# mainboard.net
KiCad netlist of a schematic drawn in EAGLE
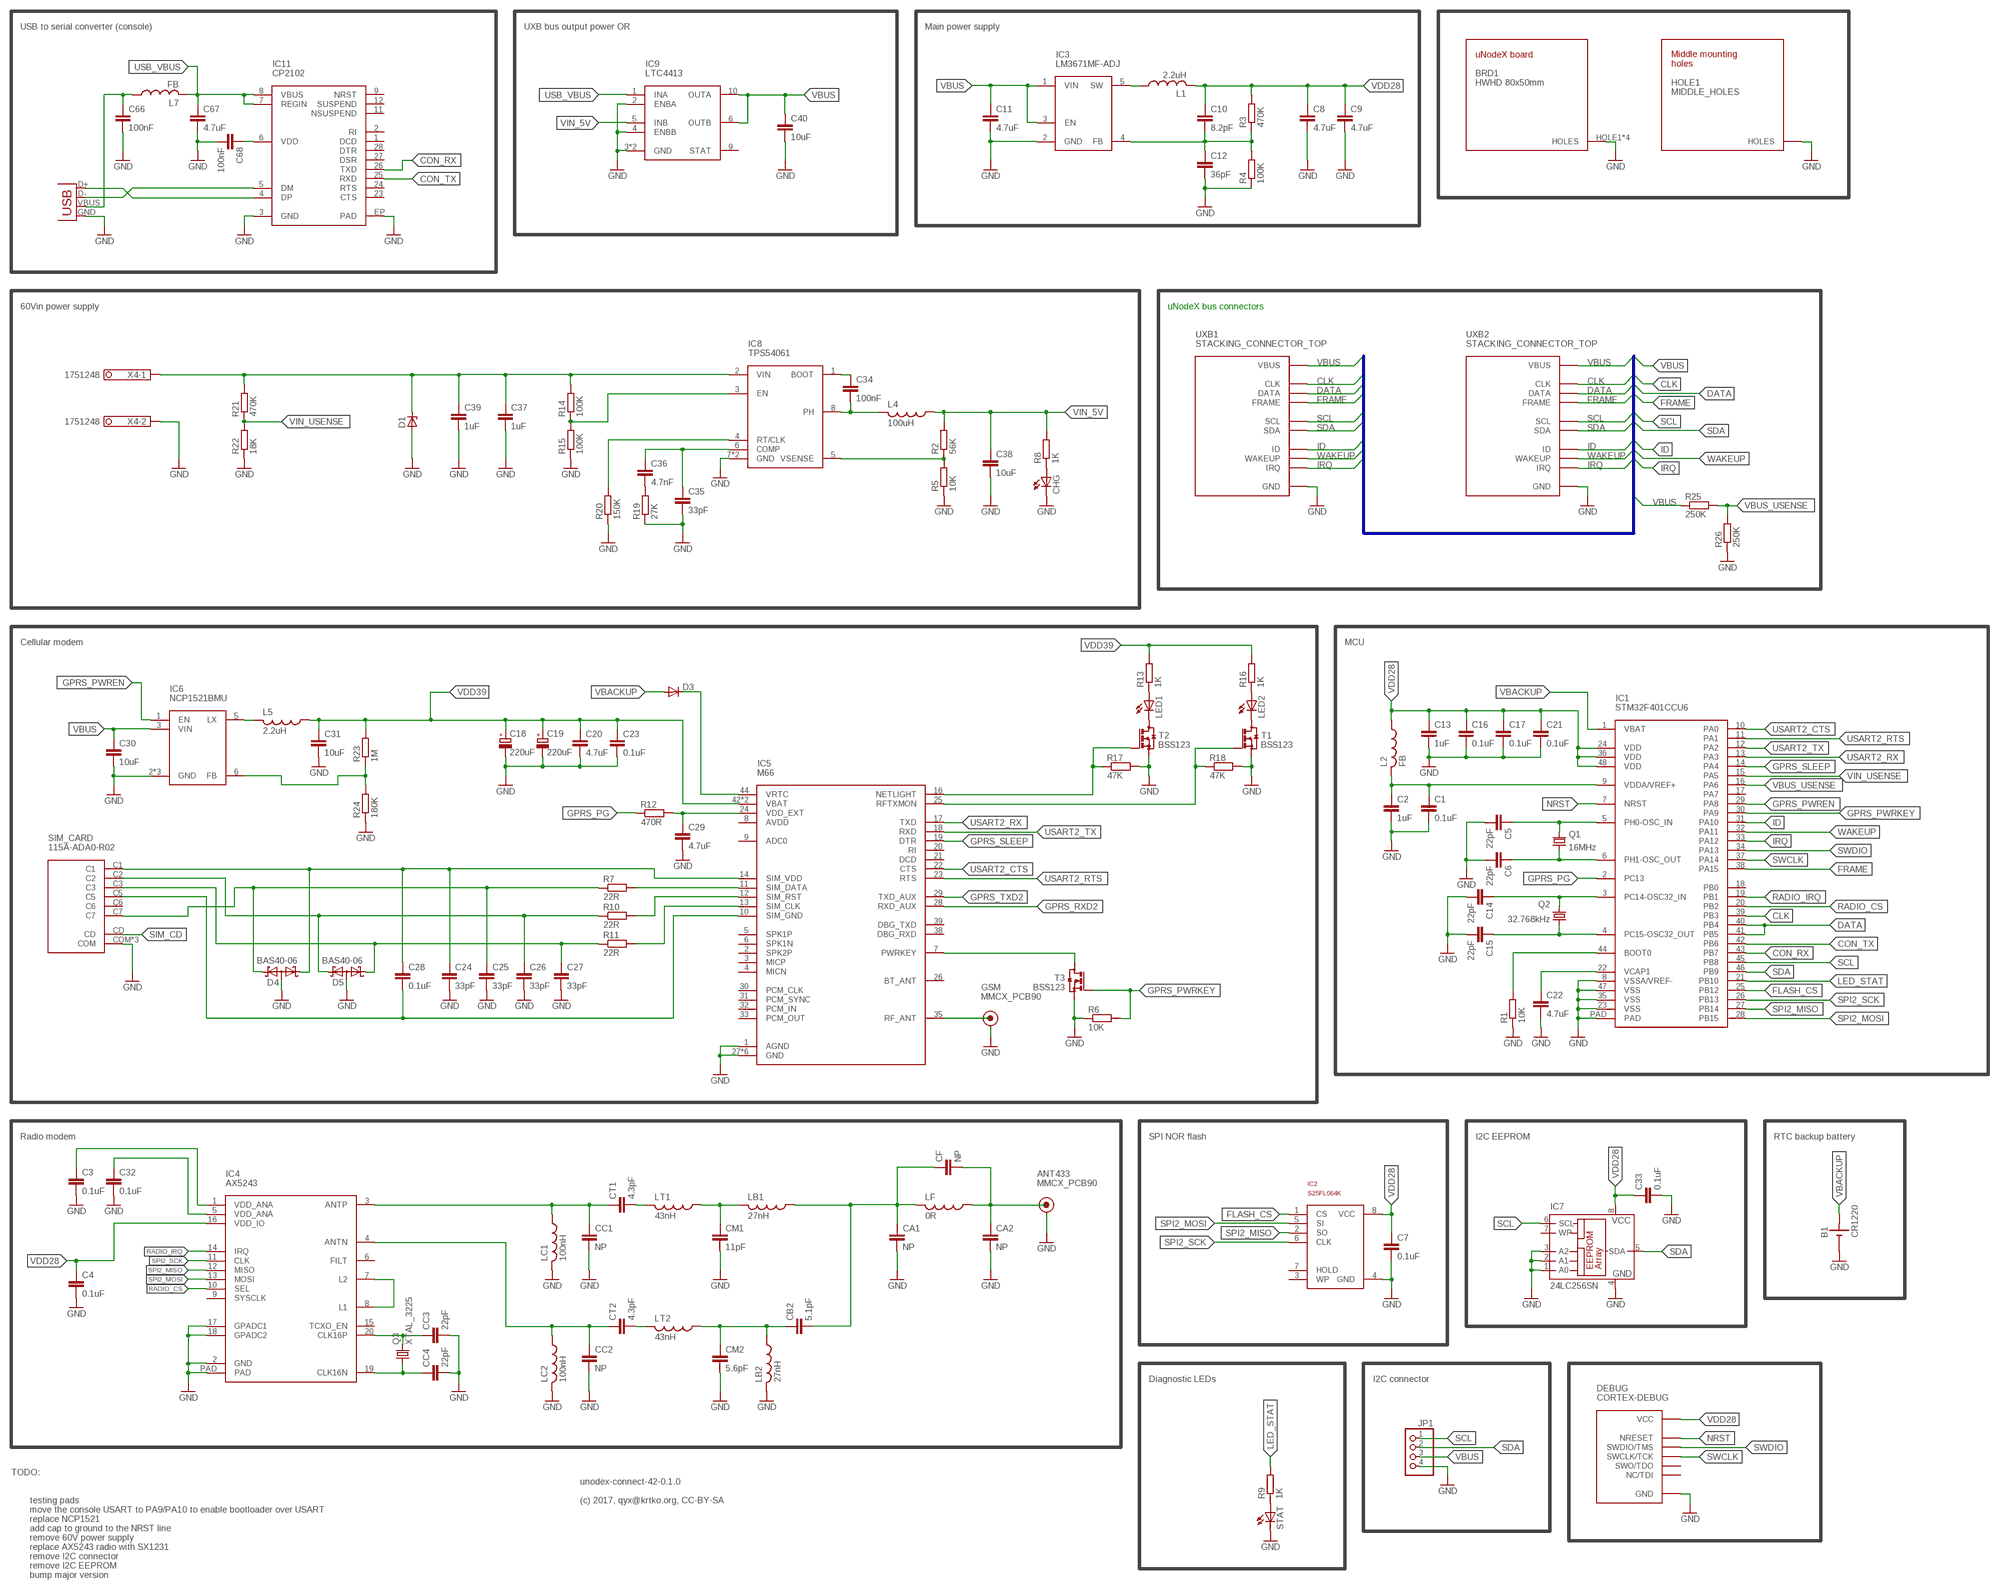
[diagram p0: schematic, sheet 1]

(export (version "E")
  (design (tool "Eeschema 10.0.6"))
  (components
    (comp (ref "ANT433")
      (value "MMCX_PCB90")
      (footprint "eagle-import:MMCX_PCB_90")
      (libsource (lib "eagle-import") (part "MMCX_PCB90"))
    )
    (comp (ref "B1")
      (value "CR1220")
      (footprint "eagle-import:CONNFLY_CR1220")
      (libsource (lib "eagle-import") (part "CONNFLY_CR1220"))
    )
    (comp (ref "BRD1")
      (value "HWHD 80x50mm")
      (footprint "eagle-import:HWHD_SHARP_CORNERS")
      (libsource (lib "eagle-import") (part "BOARD_STACKINGHWHD_SH"))
    )
    (comp (ref "C1")
      (value "0.1uF")
      (footprint "eagle-import:C0603")
      (libsource (lib "eagle-import") (part "C-EUC0603"))
    )
    (comp (ref "C2")
      (value "1uF")
      (footprint "eagle-import:C0603")
      (libsource (lib "eagle-import") (part "C-EUC0603"))
    )
    (comp (ref "C3")
      (value "0.1uF")
      (footprint "eagle-import:C0603")
      (libsource (lib "eagle-import") (part "C-EUC0603"))
    )
    (comp (ref "C4")
      (value "0.1uF")
      (footprint "eagle-import:C0603")
      (libsource (lib "eagle-import") (part "C-EUC0603"))
    )
    (comp (ref "C5")
      (value "22pF")
      (footprint "eagle-import:C0603")
      (libsource (lib "eagle-import") (part "C-EUC0603"))
    )
    (comp (ref "C6")
      (value "22pF")
      (footprint "eagle-import:C0603")
      (libsource (lib "eagle-import") (part "C-EUC0603"))
    )
    (comp (ref "C7")
      (value "0.1uF")
      (footprint "eagle-import:C0603")
      (libsource (lib "eagle-import") (part "C-EUC0603"))
    )
    (comp (ref "C8")
      (value "4.7uF")
      (footprint "eagle-import:C0805")
      (libsource (lib "eagle-import") (part "C-EUC0805"))
    )
    (comp (ref "C9")
      (value "4.7uF")
      (footprint "eagle-import:C0805")
      (libsource (lib "eagle-import") (part "C-EUC0805"))
    )
    (comp (ref "C10")
      (value "8.2pF")
      (footprint "eagle-import:C0603")
      (libsource (lib "eagle-import") (part "C-EUC0603"))
    )
    (comp (ref "C11")
      (value "4.7uF")
      (footprint "eagle-import:C0805")
      (libsource (lib "eagle-import") (part "C-EUC0805"))
    )
    (comp (ref "C12")
      (value "36pF")
      (footprint "eagle-import:C0603")
      (libsource (lib "eagle-import") (part "C-EUC0603"))
    )
    (comp (ref "C13")
      (value "1uF")
      (footprint "eagle-import:C0603")
      (libsource (lib "eagle-import") (part "C-EUC0603"))
    )
    (comp (ref "C14")
      (value "22pF")
      (footprint "eagle-import:C0603")
      (libsource (lib "eagle-import") (part "C-EUC0603"))
    )
    (comp (ref "C15")
      (value "22pF")
      (footprint "eagle-import:C0603")
      (libsource (lib "eagle-import") (part "C-EUC0603"))
    )
    (comp (ref "C16")
      (value "0.1uF")
      (footprint "eagle-import:C0603")
      (libsource (lib "eagle-import") (part "C-EUC0603"))
    )
    (comp (ref "C17")
      (value "0.1uF")
      (footprint "eagle-import:C0603")
      (libsource (lib "eagle-import") (part "C-EUC0603"))
    )
    (comp (ref "C18")
      (value "220uF")
      (footprint "eagle-import:PANASONIC_D")
      (libsource (lib "eagle-import") (part "CPOL-EUD"))
    )
    (comp (ref "C19")
      (value "220uF")
      (footprint "eagle-import:PANASONIC_D")
      (libsource (lib "eagle-import") (part "CPOL-EUD"))
    )
    (comp (ref "C20")
      (value "4.7uF")
      (footprint "eagle-import:C0805")
      (libsource (lib "eagle-import") (part "C-EUC0805"))
    )
    (comp (ref "C21")
      (value "0.1uF")
      (footprint "eagle-import:C0603")
      (libsource (lib "eagle-import") (part "C-EUC0603"))
    )
    (comp (ref "C22")
      (value "4.7uF")
      (footprint "eagle-import:C0603")
      (libsource (lib "eagle-import") (part "C-EUC0603"))
    )
    (comp (ref "C23")
      (value "0.1uF")
      (footprint "eagle-import:C0603")
      (libsource (lib "eagle-import") (part "C-EUC0603"))
    )
    (comp (ref "C24")
      (value "33pF")
      (footprint "eagle-import:C0603")
      (libsource (lib "eagle-import") (part "C-EUC0603"))
    )
    (comp (ref "C25")
      (value "33pF")
      (footprint "eagle-import:C0603")
      (libsource (lib "eagle-import") (part "C-EUC0603"))
    )
    (comp (ref "C26")
      (value "33pF")
      (footprint "eagle-import:C0603")
      (libsource (lib "eagle-import") (part "C-EUC0603"))
    )
    (comp (ref "C27")
      (value "33pF")
      (footprint "eagle-import:C0603")
      (libsource (lib "eagle-import") (part "C-EUC0603"))
    )
    (comp (ref "C28")
      (value "0.1uF")
      (footprint "eagle-import:C0603")
      (libsource (lib "eagle-import") (part "C-EUC0603"))
    )
    (comp (ref "C29")
      (value "4.7uF")
      (footprint "eagle-import:C0805")
      (libsource (lib "eagle-import") (part "C-EUC0805"))
    )
    (comp (ref "C30")
      (value "10uF")
      (footprint "eagle-import:C1206")
      (libsource (lib "eagle-import") (part "C-EUC1206"))
    )
    (comp (ref "C31")
      (value "10uF")
      (footprint "eagle-import:C1206")
      (libsource (lib "eagle-import") (part "C-EUC1206"))
    )
    (comp (ref "C32")
      (value "0.1uF")
      (footprint "eagle-import:C0603")
      (libsource (lib "eagle-import") (part "C-EUC0603"))
    )
    (comp (ref "C33")
      (value "0.1uF")
      (footprint "eagle-import:C0603")
      (libsource (lib "eagle-import") (part "C-EUC0603"))
    )
    (comp (ref "C34")
      (value "100nF")
      (footprint "eagle-import:C0603")
      (libsource (lib "eagle-import") (part "C-EUC0603"))
    )
    (comp (ref "C35")
      (value "33pF")
      (footprint "eagle-import:C0603")
      (libsource (lib "eagle-import") (part "C-EUC0603"))
    )
    (comp (ref "C36")
      (value "4.7nF")
      (footprint "eagle-import:C0603")
      (libsource (lib "eagle-import") (part "C-EUC0603"))
    )
    (comp (ref "C37")
      (value "1uF")
      (footprint "eagle-import:C1206")
      (libsource (lib "eagle-import") (part "C-EUC1206"))
    )
    (comp (ref "C38")
      (value "10uF")
      (footprint "eagle-import:C1206")
      (libsource (lib "eagle-import") (part "C-EUC1206"))
    )
    (comp (ref "C39")
      (value "1uF")
      (footprint "eagle-import:C1206")
      (libsource (lib "eagle-import") (part "C-EUC1206"))
    )
    (comp (ref "C40")
      (value "10uF")
      (footprint "eagle-import:C0805")
      (libsource (lib "eagle-import") (part "C-EUC0805"))
    )
    (comp (ref "C66")
      (value "100nF")
      (footprint "eagle-import:C0603")
      (libsource (lib "eagle-import") (part "C-EUC0603"))
    )
    (comp (ref "C67")
      (value "4.7uF")
      (footprint "eagle-import:C0805")
      (libsource (lib "eagle-import") (part "C-EUC0805"))
    )
    (comp (ref "C68")
      (value "100nF")
      (footprint "eagle-import:C0603")
      (libsource (lib "eagle-import") (part "C-EUC0603"))
    )
    (comp (ref "CA1")
      (value "NP")
      (footprint "eagle-import:C0603")
      (libsource (lib "eagle-import") (part "C-EUC0603"))
    )
    (comp (ref "CA2")
      (value "NP")
      (footprint "eagle-import:C0603")
      (libsource (lib "eagle-import") (part "C-EUC0603"))
    )
    (comp (ref "CB2")
      (value "5.1pF")
      (footprint "eagle-import:C0603")
      (libsource (lib "eagle-import") (part "C-EUC0603"))
    )
    (comp (ref "CC1")
      (value "NP")
      (footprint "eagle-import:C0603")
      (libsource (lib "eagle-import") (part "C-EUC0603"))
    )
    (comp (ref "CC2")
      (value "NP")
      (footprint "eagle-import:C0603")
      (libsource (lib "eagle-import") (part "C-EUC0603"))
    )
    (comp (ref "CC3")
      (value "22pF")
      (footprint "eagle-import:C0603")
      (libsource (lib "eagle-import") (part "C-EUC0603"))
    )
    (comp (ref "CC4")
      (value "22pF")
      (footprint "eagle-import:C0603")
      (libsource (lib "eagle-import") (part "C-EUC0603"))
    )
    (comp (ref "CF")
      (value "NP")
      (footprint "eagle-import:C0603")
      (libsource (lib "eagle-import") (part "C-EUC0603"))
    )
    (comp (ref "CHG")
      (value "LEDCHIPLED_0805")
      (footprint "eagle-import:CHIPLED_0805")
      (libsource (lib "eagle-import") (part "LEDCHIPLED_0805"))
    )
    (comp (ref "CM1")
      (value "11pF")
      (footprint "eagle-import:C0603")
      (libsource (lib "eagle-import") (part "C-EUC0603"))
    )
    (comp (ref "CM2")
      (value "5.6pF")
      (footprint "eagle-import:C0603")
      (libsource (lib "eagle-import") (part "C-EUC0603"))
    )
    (comp (ref "CT1")
      (value "4.3pF")
      (footprint "eagle-import:C0603")
      (libsource (lib "eagle-import") (part "C-EUC0603"))
    )
    (comp (ref "CT2")
      (value "4.3pF")
      (footprint "eagle-import:C0603")
      (libsource (lib "eagle-import") (part "C-EUC0603"))
    )
    (comp (ref "D1")
      (value "ZENER-DIODESMB")
      (footprint "eagle-import:SMB")
      (libsource (lib "eagle-import") (part "ZENER-DIODESMB"))
    )
    (comp (ref "D3")
      (value "DIODE-SOD123")
      (footprint "eagle-import:SOD123")
      (libsource (lib "eagle-import") (part "DIODE-SOD123"))
    )
    (comp (ref "D4")
      (value "BAS40-06")
      (footprint "eagle-import:SOT23")
      (libsource (lib "eagle-import") (part "BAS40-06"))
    )
    (comp (ref "D5")
      (value "BAS40-06")
      (footprint "eagle-import:SOT23")
      (libsource (lib "eagle-import") (part "BAS40-06"))
    )
    (comp (ref "DEBUG")
      (value "CORTEX-DEBUG")
      (footprint "eagle-import:CORTEX-DEBUG")
      (libsource (lib "eagle-import") (part "CORTEX-DEBUG"))
    )
    (comp (ref "GSM")
      (value "MMCX_PCB90")
      (footprint "eagle-import:MMCX_PCB_90")
      (libsource (lib "eagle-import") (part "MMCX_PCB90"))
    )
    (comp (ref "HOLE1")
      (value "MIDDLE_HOLES")
      (footprint "eagle-import:MIDDLE_HOLES")
      (libsource (lib "eagle-import") (part "MIDDLE_HOLES"))
    )
    (comp (ref "IC1")
      (value "STM32F401CCU6")
      (footprint "eagle-import:UFQFPN48")
      (libsource (lib "eagle-import") (part "STM32F401CCU6"))
    )
    (comp (ref "IC2")
      (value "S25FL064K")
      (footprint "eagle-import:SO-08M")
      (libsource (lib "eagle-import") (part "S25FL064K"))
    )
    (comp (ref "IC3")
      (value "LM3671MF-ADJ")
      (footprint "eagle-import:SOT23-5")
      (libsource (lib "eagle-import") (part "LM3671MF"))
    )
    (comp (ref "IC4")
      (value "AX5243")
      (footprint "eagle-import:QFN20")
      (libsource (lib "eagle-import") (part "AX5243"))
    )
    (comp (ref "IC5")
      (value "M66")
      (footprint "eagle-import:M66")
      (libsource (lib "eagle-import") (part "M66"))
    )
    (comp (ref "IC6")
      (value "NCP1521BMU")
      (footprint "eagle-import:UDFN6")
      (libsource (lib "eagle-import") (part "NCP1521BMU"))
    )
    (comp (ref "IC7")
      (value "24LC256SN")
      (footprint "eagle-import:SO-08")
      (fields (field (name "MF") "MICROCHIP") (field (name "MPN") "24LC256-I/SN"))
      (libsource (lib "eagle-import") (part "24SNLC256"))
    )
    (comp (ref "IC8")
      (value "TPS54061")
      (footprint "eagle-import:WSON8")
      (libsource (lib "eagle-import") (part "TPS54061"))
    )
    (comp (ref "IC9")
      (value "LTC4413")
      (footprint "eagle-import:DFN10")
      (libsource (lib "eagle-import") (part "LTC4413"))
    )
    (comp (ref "IC11")
      (value "CP2102")
      (footprint "eagle-import:QFN28")
      (libsource (lib "eagle-import") (part "CP2102"))
    )
    (comp (ref "JP1")
      (value "PINHD-1X4")
      (footprint "eagle-import:1X04")
      (libsource (lib "eagle-import") (part "PINHD-1X4"))
    )
    (comp (ref "L1")
      (value "2.2uH")
      (footprint "eagle-import:L2825P")
      (libsource (lib "eagle-import") (part "L-USL2825P"))
    )
    (comp (ref "L2")
      (value "FB")
      (footprint "eagle-import:L2012C")
      (libsource (lib "eagle-import") (part "L-USL2012C"))
    )
    (comp (ref "L4")
      (value "100uH")
      (footprint "eagle-import:L5650M")
      (libsource (lib "eagle-import") (part "L-USL5650M"))
    )
    (comp (ref "L5")
      (value "2.2uH")
      (footprint "eagle-import:L2825P")
      (libsource (lib "eagle-import") (part "L-USL2825P"))
    )
    (comp (ref "L7")
      (value "FB")
      (footprint "eagle-import:L2012C")
      (libsource (lib "eagle-import") (part "L-USL2012C"))
    )
    (comp (ref "LB1")
      (value "27nH")
      (footprint "eagle-import:L2012C")
      (libsource (lib "eagle-import") (part "L-USL2012C"))
    )
    (comp (ref "LB2")
      (value "27nH")
      (footprint "eagle-import:L2012C")
      (libsource (lib "eagle-import") (part "L-USL2012C"))
    )
    (comp (ref "LC1")
      (value "100nH")
      (footprint "eagle-import:L2012C")
      (libsource (lib "eagle-import") (part "L-USL2012C"))
    )
    (comp (ref "LC2")
      (value "100nH")
      (footprint "eagle-import:L2012C")
      (libsource (lib "eagle-import") (part "L-USL2012C"))
    )
    (comp (ref "LED1")
      (value "LEDCHIP-LED0805")
      (footprint "eagle-import:CHIP-LED0805")
      (libsource (lib "eagle-import") (part "LEDCHIP-LED0805"))
    )
    (comp (ref "LED2")
      (value "LEDCHIP-LED0805")
      (footprint "eagle-import:CHIP-LED0805")
      (libsource (lib "eagle-import") (part "LEDCHIP-LED0805"))
    )
    (comp (ref "LF")
      (value "0R")
      (footprint "eagle-import:L2012C")
      (libsource (lib "eagle-import") (part "L-USL2012C"))
    )
    (comp (ref "LT1")
      (value "43nH")
      (footprint "eagle-import:L2012C")
      (libsource (lib "eagle-import") (part "L-USL2012C"))
    )
    (comp (ref "LT2")
      (value "43nH")
      (footprint "eagle-import:L2012C")
      (libsource (lib "eagle-import") (part "L-USL2012C"))
    )
    (comp (ref "Q1")
      (value "16MHz")
      (footprint "eagle-import:XTAL_3225")
      (libsource (lib "eagle-import") (part "XTAL_3225"))
    )
    (comp (ref "Q2")
      (value "32.768kHz")
      (footprint "eagle-import:TC26H")
      (libsource (lib "eagle-import") (part "CRYSTALTC26H"))
    )
    (comp (ref "Q3")
      (value "XTAL_3225")
      (footprint "eagle-import:XTAL_3225")
      (libsource (lib "eagle-import") (part "XTAL_3225"))
    )
    (comp (ref "R1")
      (value "10K")
      (footprint "eagle-import:R0603")
      (libsource (lib "eagle-import") (part "R-EU_R0603"))
    )
    (comp (ref "R2")
      (value "56K")
      (footprint "eagle-import:R0603")
      (libsource (lib "eagle-import") (part "R-EU_R0603"))
    )
    (comp (ref "R3")
      (value "470K")
      (footprint "eagle-import:R0603")
      (libsource (lib "eagle-import") (part "R-EU_R0603"))
    )
    (comp (ref "R4")
      (value "100K")
      (footprint "eagle-import:R0603")
      (libsource (lib "eagle-import") (part "R-EU_R0603"))
    )
    (comp (ref "R5")
      (value "10K")
      (footprint "eagle-import:R0603")
      (libsource (lib "eagle-import") (part "R-EU_R0603"))
    )
    (comp (ref "R6")
      (value "10K")
      (footprint "eagle-import:R0603")
      (libsource (lib "eagle-import") (part "R-EU_R0603"))
    )
    (comp (ref "R7")
      (value "22R")
      (footprint "eagle-import:R0603")
      (libsource (lib "eagle-import") (part "R-EU_R0603"))
    )
    (comp (ref "R8")
      (value "1K")
      (footprint "eagle-import:R0603")
      (libsource (lib "eagle-import") (part "R-EU_R0603"))
    )
    (comp (ref "R9")
      (value "1K")
      (footprint "eagle-import:R0603")
      (libsource (lib "eagle-import") (part "R-EU_R0603"))
    )
    (comp (ref "R10")
      (value "22R")
      (footprint "eagle-import:R0603")
      (libsource (lib "eagle-import") (part "R-EU_R0603"))
    )
    (comp (ref "R11")
      (value "22R")
      (footprint "eagle-import:R0603")
      (libsource (lib "eagle-import") (part "R-EU_R0603"))
    )
    (comp (ref "R12")
      (value "470R")
      (footprint "eagle-import:R0603")
      (libsource (lib "eagle-import") (part "R-EU_R0603"))
    )
    (comp (ref "R13")
      (value "1K")
      (footprint "eagle-import:R0603")
      (libsource (lib "eagle-import") (part "R-EU_R0603"))
    )
    (comp (ref "R14")
      (value "100K")
      (footprint "eagle-import:R0603")
      (libsource (lib "eagle-import") (part "R-EU_R0603"))
    )
    (comp (ref "R15")
      (value "100K")
      (footprint "eagle-import:R0603")
      (libsource (lib "eagle-import") (part "R-EU_R0603"))
    )
    (comp (ref "R16")
      (value "1K")
      (footprint "eagle-import:R0603")
      (libsource (lib "eagle-import") (part "R-EU_R0603"))
    )
    (comp (ref "R17")
      (value "47K")
      (footprint "eagle-import:R0603")
      (libsource (lib "eagle-import") (part "R-EU_R0603"))
    )
    (comp (ref "R18")
      (value "47K")
      (footprint "eagle-import:R0603")
      (libsource (lib "eagle-import") (part "R-EU_R0603"))
    )
    (comp (ref "R19")
      (value "27K")
      (footprint "eagle-import:R0603")
      (libsource (lib "eagle-import") (part "R-EU_R0603"))
    )
    (comp (ref "R20")
      (value "150K")
      (footprint "eagle-import:R0603")
      (libsource (lib "eagle-import") (part "R-EU_R0603"))
    )
    (comp (ref "R21")
      (value "470K")
      (footprint "eagle-import:R0603")
      (libsource (lib "eagle-import") (part "R-EU_R0603"))
    )
    (comp (ref "R22")
      (value "18K")
      (footprint "eagle-import:R0603")
      (libsource (lib "eagle-import") (part "R-EU_R0603"))
    )
    (comp (ref "R23")
      (value "1M")
      (footprint "eagle-import:R0603")
      (libsource (lib "eagle-import") (part "R-EU_R0603"))
    )
    (comp (ref "R24")
      (value "180K")
      (footprint "eagle-import:R0603")
      (libsource (lib "eagle-import") (part "R-EU_R0603"))
    )
    (comp (ref "R25")
      (value "250K")
      (footprint "eagle-import:R0603")
      (libsource (lib "eagle-import") (part "R-EU_R0603"))
    )
    (comp (ref "R26")
      (value "250K")
      (footprint "eagle-import:R0603")
      (libsource (lib "eagle-import") (part "R-EU_R0603"))
    )
    (comp (ref "SIM_CARD")
      (value "115A-ADA0-R02")
      (footprint "eagle-import:115A-ADA0-R02")
      (libsource (lib "eagle-import") (part "115A-ADA0-R02"))
    )
    (comp (ref "STAT")
      (value "LEDCHIPLED_0805")
      (footprint "eagle-import:CHIPLED_0805")
      (libsource (lib "eagle-import") (part "LEDCHIPLED_0805"))
    )
    (comp (ref "T1")
      (value "BSS123")
      (footprint "eagle-import:SOT23")
      (libsource (lib "eagle-import") (part "BSS123"))
    )
    (comp (ref "T2")
      (value "BSS123")
      (footprint "eagle-import:SOT23")
      (libsource (lib "eagle-import") (part "BSS123"))
    )
    (comp (ref "T3")
      (value "BSS123")
      (footprint "eagle-import:SOT23")
      (libsource (lib "eagle-import") (part "BSS123"))
    )
    (comp (ref "UXB1")
      (value "STACKING_CONNECTOR_TOP")
      (footprint "eagle-import:HAR-FLEX-TOP-12P")
      (libsource (lib "eagle-import") (part "STACKING_CONNECTOR_TOP"))
    )
    (comp (ref "UXB2")
      (value "STACKING_CONNECTOR_TOP")
      (footprint "eagle-import:HAR-FLEX-TOP-12P")
      (libsource (lib "eagle-import") (part "STACKING_CONNECTOR_TOP"))
    )
    (comp (ref "X4")
      (value "1751248")
      (footprint "eagle-import:1751248")
      (libsource (lib "eagle-import") (part "1751248"))
    )
    (comp (ref "X5")
      (value "USB-MICROB")
      (footprint "eagle-import:USB-MICROB")
      (libsource (lib "eagle-import") (part "USB-MICROB"))
    )
  )
  (nets
    (net (code "1") (name "CLK") (class "Default")
      (node (ref "IC1") (pin "39") (pinfunction "PB3_39") (pintype "bidirectional"))
      (node (ref "UXB1") (pin "CLK") (pinfunction "CLK_CLK") (pintype "bidirectional"))
      (node (ref "UXB2") (pin "CLK") (pinfunction "CLK_CLK") (pintype "bidirectional"))
    )
    (net (code "2") (name "CON_RX") (class "Default")
      (node (ref "IC1") (pin "43") (pinfunction "PB7_43") (pintype "bidirectional"))
      (node (ref "IC11") (pin "26") (pinfunction "TXD_26") (pintype "bidirectional"))
    )
    (net (code "3") (name "CON_TX") (class "Default")
      (node (ref "IC1") (pin "42") (pinfunction "PB6_42") (pintype "bidirectional"))
      (node (ref "IC11") (pin "25") (pinfunction "RXD_25") (pintype "bidirectional"))
    )
    (net (code "4") (name "DATA") (class "Default")
      (node (ref "IC1") (pin "40") (pinfunction "PB4_40") (pintype "bidirectional"))
      (node (ref "IC1") (pin "41") (pinfunction "PB5_41") (pintype "bidirectional"))
      (node (ref "UXB1") (pin "DATA") (pinfunction "DATA_DATA") (pintype "bidirectional"))
      (node (ref "UXB2") (pin "DATA") (pinfunction "DATA_DATA") (pintype "bidirectional"))
    )
    (net (code "5") (name "FLASH_CS") (class "Default")
      (node (ref "IC1") (pin "25") (pinfunction "PB12_25") (pintype "bidirectional"))
      (node (ref "IC2") (pin "1") (pinfunction "CS_1") (pintype "bidirectional"))
    )
    (net (code "6") (name "FRAME") (class "Default")
      (node (ref "IC1") (pin "38") (pinfunction "PA15_38") (pintype "bidirectional"))
      (node (ref "UXB1") (pin "FRAME") (pinfunction "FRAME_FRAME") (pintype "bidirectional"))
      (node (ref "UXB2") (pin "FRAME") (pinfunction "FRAME_FRAME") (pintype "bidirectional"))
    )
    (net (code "7") (name "GND") (class "Default")
      (node (ref "ANT433") (pin "S1") (pinfunction "SHIELD_S1") (pintype "bidirectional"))
      (node (ref "ANT433") (pin "S2") (pinfunction "SHIELD_S2") (pintype "bidirectional"))
      (node (ref "ANT433") (pin "S3") (pinfunction "SHIELD_S3") (pintype "bidirectional"))
      (node (ref "ANT433") (pin "S4") (pinfunction "SHIELD_S4") (pintype "bidirectional"))
      (node (ref "B1") (pin "NEG") (pinfunction "-_NEG") (pintype "passive"))
      (node (ref "BRD1") (pin "HOLE1") (pinfunction "HOLES_HOLE1") (pintype "bidirectional"))
      (node (ref "BRD1") (pin "HOLE2") (pinfunction "HOLES_HOLE2") (pintype "bidirectional"))
      (node (ref "BRD1") (pin "HOLE3") (pinfunction "HOLES_HOLE3") (pintype "bidirectional"))
      (node (ref "BRD1") (pin "HOLE4") (pinfunction "HOLES_HOLE4") (pintype "bidirectional"))
      (node (ref "C1") (pin "2") (pinfunction "2_2") (pintype "passive"))
      (node (ref "C11") (pin "2") (pinfunction "2_2") (pintype "passive"))
      (node (ref "C12") (pin "2") (pinfunction "2_2") (pintype "passive"))
      (node (ref "C13") (pin "2") (pinfunction "2_2") (pintype "passive"))
      (node (ref "C14") (pin "2") (pinfunction "2_2") (pintype "passive"))
      (node (ref "C15") (pin "2") (pinfunction "2_2") (pintype "passive"))
      (node (ref "C16") (pin "2") (pinfunction "2_2") (pintype "passive"))
      (node (ref "C17") (pin "2") (pinfunction "2_2") (pintype "passive"))
      (node (ref "C18") (pin "-") (pinfunction "-_-") (pintype "passive"))
      (node (ref "C19") (pin "-") (pinfunction "-_-") (pintype "passive"))
      (node (ref "C2") (pin "2") (pinfunction "2_2") (pintype "passive"))
      (node (ref "C20") (pin "2") (pinfunction "2_2") (pintype "passive"))
      (node (ref "C21") (pin "2") (pinfunction "2_2") (pintype "passive"))
      (node (ref "C22") (pin "2") (pinfunction "2_2") (pintype "passive"))
      (node (ref "C23") (pin "2") (pinfunction "2_2") (pintype "passive"))
      (node (ref "C24") (pin "2") (pinfunction "2_2") (pintype "passive"))
      (node (ref "C25") (pin "2") (pinfunction "2_2") (pintype "passive"))
      (node (ref "C26") (pin "2") (pinfunction "2_2") (pintype "passive"))
      (node (ref "C27") (pin "2") (pinfunction "2_2") (pintype "passive"))
      (node (ref "C29") (pin "2") (pinfunction "2_2") (pintype "passive"))
      (node (ref "C3") (pin "2") (pinfunction "2_2") (pintype "passive"))
      (node (ref "C30") (pin "2") (pinfunction "2_2") (pintype "passive"))
      (node (ref "C31") (pin "2") (pinfunction "2_2") (pintype "passive"))
      (node (ref "C32") (pin "2") (pinfunction "2_2") (pintype "passive"))
      (node (ref "C33") (pin "2") (pinfunction "2_2") (pintype "passive"))
      (node (ref "C35") (pin "2") (pinfunction "2_2") (pintype "passive"))
      (node (ref "C37") (pin "2") (pinfunction "2_2") (pintype "passive"))
      (node (ref "C38") (pin "2") (pinfunction "2_2") (pintype "passive"))
      (node (ref "C39") (pin "2") (pinfunction "2_2") (pintype "passive"))
      (node (ref "C4") (pin "2") (pinfunction "2_2") (pintype "passive"))
      (node (ref "C40") (pin "2") (pinfunction "2_2") (pintype "passive"))
      (node (ref "C5") (pin "2") (pinfunction "2_2") (pintype "passive"))
      (node (ref "C6") (pin "2") (pinfunction "2_2") (pintype "passive"))
      (node (ref "C66") (pin "2") (pinfunction "2_2") (pintype "passive"))
      (node (ref "C67") (pin "2") (pinfunction "2_2") (pintype "passive"))
      (node (ref "C68") (pin "2") (pinfunction "2_2") (pintype "passive"))
      (node (ref "C7") (pin "2") (pinfunction "2_2") (pintype "passive"))
      (node (ref "C8") (pin "2") (pinfunction "2_2") (pintype "passive"))
      (node (ref "C9") (pin "2") (pinfunction "2_2") (pintype "passive"))
      (node (ref "CA1") (pin "2") (pinfunction "2_2") (pintype "passive"))
      (node (ref "CA2") (pin "2") (pinfunction "2_2") (pintype "passive"))
      (node (ref "CC1") (pin "2") (pinfunction "2_2") (pintype "passive"))
      (node (ref "CC2") (pin "2") (pinfunction "2_2") (pintype "passive"))
      (node (ref "CC3") (pin "2") (pinfunction "2_2") (pintype "passive"))
      (node (ref "CC4") (pin "2") (pinfunction "2_2") (pintype "passive"))
      (node (ref "CHG") (pin "C") (pinfunction "C_C") (pintype "passive"))
      (node (ref "CM1") (pin "2") (pinfunction "2_2") (pintype "passive"))
      (node (ref "CM2") (pin "2") (pinfunction "2_2") (pintype "passive"))
      (node (ref "D1") (pin "A") (pinfunction "A_A") (pintype "passive"))
      (node (ref "D4") (pin "3") (pinfunction "AA_3") (pintype "passive"))
      (node (ref "D5") (pin "3") (pinfunction "AA_3") (pintype "passive"))
      (node (ref "DEBUG") (pin "GND1") (pinfunction "GND_GND1") (pintype "bidirectional"))
      (node (ref "DEBUG") (pin "GND2") (pinfunction "GND_GND2") (pintype "bidirectional"))
      (node (ref "DEBUG") (pin "GND_DETECT") (pinfunction "GND_GND_DETECT") (pintype "bidirectional"))
      (node (ref "GSM") (pin "S1") (pinfunction "SHIELD_S1") (pintype "bidirectional"))
      (node (ref "GSM") (pin "S2") (pinfunction "SHIELD_S2") (pintype "bidirectional"))
      (node (ref "GSM") (pin "S3") (pinfunction "SHIELD_S3") (pintype "bidirectional"))
      (node (ref "GSM") (pin "S4") (pinfunction "SHIELD_S4") (pintype "bidirectional"))
      (node (ref "HOLE1") (pin "P$1") (pinfunction "HOLES_P$1") (pintype "bidirectional"))
      (node (ref "HOLE1") (pin "P$2") (pinfunction "HOLES_P$2") (pintype "bidirectional"))
      (node (ref "HOLE1") (pin "P$3") (pinfunction "HOLES_P$3") (pintype "bidirectional"))
      (node (ref "HOLE1") (pin "P$4") (pinfunction "HOLES_P$4") (pintype "bidirectional"))
      (node (ref "IC1") (pin "23") (pinfunction "VSS_23") (pintype "bidirectional"))
      (node (ref "IC1") (pin "35") (pinfunction "VSS_35") (pintype "bidirectional"))
      (node (ref "IC1") (pin "47") (pinfunction "VSS_47") (pintype "bidirectional"))
      (node (ref "IC1") (pin "8") (pinfunction "VSSA/VREF-_8") (pintype "bidirectional"))
      (node (ref "IC1") (pin "PAD") (pinfunction "PAD_PAD") (pintype "bidirectional"))
      (node (ref "IC11") (pin "3") (pinfunction "GND_3") (pintype "bidirectional"))
      (node (ref "IC11") (pin "EP") (pinfunction "PAD_EP") (pintype "bidirectional"))
      (node (ref "IC2") (pin "4") (pinfunction "GND_4") (pintype "power_in"))
      (node (ref "IC3") (pin "2") (pinfunction "GND_2") (pintype "bidirectional"))
      (node (ref "IC4") (pin "17") (pinfunction "GPADC1_17") (pintype "bidirectional"))
      (node (ref "IC4") (pin "18") (pinfunction "GPADC2_18") (pintype "bidirectional"))
      (node (ref "IC4") (pin "2") (pinfunction "GND_2") (pintype "bidirectional"))
      (node (ref "IC4") (pin "PAD") (pinfunction "PAD_PAD") (pintype "bidirectional"))
      (node (ref "IC5") (pin "1") (pinfunction "AGND_1") (pintype "bidirectional"))
      (node (ref "IC5") (pin "27") (pinfunction "GND_27") (pintype "bidirectional"))
      (node (ref "IC5") (pin "34") (pinfunction "GND_34") (pintype "bidirectional"))
      (node (ref "IC5") (pin "36") (pinfunction "GND_36") (pintype "bidirectional"))
      (node (ref "IC5") (pin "37") (pinfunction "GND_37") (pintype "bidirectional"))
      (node (ref "IC5") (pin "40") (pinfunction "GND_40") (pintype "bidirectional"))
      (node (ref "IC5") (pin "41") (pinfunction "GND_41") (pintype "bidirectional"))
      (node (ref "IC6") (pin "2") (pinfunction "GND_2") (pintype "bidirectional"))
      (node (ref "IC6") (pin "4") (pinfunction "GND_4") (pintype "bidirectional"))
      (node (ref "IC6") (pin "PAD") (pinfunction "GND_PAD") (pintype "bidirectional"))
      (node (ref "IC7") (pin "1") (pinfunction "A0_1") (pintype "input"))
      (node (ref "IC7") (pin "2") (pinfunction "A1_2") (pintype "input"))
      (node (ref "IC7") (pin "3") (pinfunction "A2_3") (pintype "input"))
      (node (ref "IC7") (pin "4") (pinfunction "GND_4") (pintype "power_in"))
      (node (ref "IC8") (pin "7") (pinfunction "GND_7") (pintype "bidirectional"))
      (node (ref "IC8") (pin "PAD") (pinfunction "GND_PAD") (pintype "bidirectional"))
      (node (ref "IC9") (pin "2") (pinfunction "ENBA_2") (pintype "bidirectional"))
      (node (ref "IC9") (pin "3") (pinfunction "GND_3") (pintype "bidirectional"))
      (node (ref "IC9") (pin "4") (pinfunction "ENBB_4") (pintype "bidirectional"))
      (node (ref "IC9") (pin "PAD") (pinfunction "GND_PAD") (pintype "bidirectional"))
      (node (ref "JP1") (pin "4") (pinfunction "4_4") (pintype "passive"))
      (node (ref "LB2") (pin "2") (pinfunction "2_2") (pintype "passive"))
      (node (ref "LC1") (pin "2") (pinfunction "2_2") (pintype "passive"))
      (node (ref "LC2") (pin "2") (pinfunction "2_2") (pintype "passive"))
      (node (ref "R1") (pin "1") (pinfunction "1_1") (pintype "passive"))
      (node (ref "R15") (pin "1") (pinfunction "1_1") (pintype "passive"))
      (node (ref "R17") (pin "2") (pinfunction "2_2") (pintype "passive"))
      (node (ref "R18") (pin "2") (pinfunction "2_2") (pintype "passive"))
      (node (ref "R19") (pin "1") (pinfunction "1_1") (pintype "passive"))
      (node (ref "R20") (pin "1") (pinfunction "1_1") (pintype "passive"))
      (node (ref "R22") (pin "1") (pinfunction "1_1") (pintype "passive"))
      (node (ref "R24") (pin "1") (pinfunction "1_1") (pintype "passive"))
      (node (ref "R26") (pin "1") (pinfunction "1_1") (pintype "passive"))
      (node (ref "R4") (pin "1") (pinfunction "1_1") (pintype "passive"))
      (node (ref "R5") (pin "1") (pinfunction "1_1") (pintype "passive"))
      (node (ref "R6") (pin "1") (pinfunction "1_1") (pintype "passive"))
      (node (ref "SIM_CARD") (pin "COM") (pinfunction "COM_COM") (pintype "bidirectional"))
      (node (ref "SIM_CARD") (pin "H1") (pinfunction "COM_H1") (pintype "bidirectional"))
      (node (ref "SIM_CARD") (pin "H2") (pinfunction "COM_H2") (pintype "bidirectional"))
      (node (ref "STAT") (pin "C") (pinfunction "C_C") (pintype "passive"))
      (node (ref "T1") (pin "2") (pinfunction "S_2") (pintype "passive"))
      (node (ref "T2") (pin "2") (pinfunction "S_2") (pintype "passive"))
      (node (ref "T3") (pin "2") (pinfunction "S_2") (pintype "passive"))
      (node (ref "UXB1") (pin "GND1") (pinfunction "GND_GND1") (pintype "bidirectional"))
      (node (ref "UXB1") (pin "GND2") (pinfunction "GND_GND2") (pintype "bidirectional"))
      (node (ref "UXB1") (pin "GND3") (pinfunction "GND_GND3") (pintype "bidirectional"))
      (node (ref "UXB1") (pin "H1") (pinfunction "GND_H1") (pintype "bidirectional"))
      (node (ref "UXB1") (pin "H2") (pinfunction "GND_H2") (pintype "bidirectional"))
      (node (ref "UXB1") (pin "H3") (pinfunction "GND_H3") (pintype "bidirectional"))
      (node (ref "UXB1") (pin "H4") (pinfunction "GND_H4") (pintype "bidirectional"))
      (node (ref "UXB2") (pin "GND1") (pinfunction "GND_GND1") (pintype "bidirectional"))
      (node (ref "UXB2") (pin "GND2") (pinfunction "GND_GND2") (pintype "bidirectional"))
      (node (ref "UXB2") (pin "GND3") (pinfunction "GND_GND3") (pintype "bidirectional"))
      (node (ref "UXB2") (pin "H1") (pinfunction "GND_H1") (pintype "bidirectional"))
      (node (ref "UXB2") (pin "H2") (pinfunction "GND_H2") (pintype "bidirectional"))
      (node (ref "UXB2") (pin "H3") (pinfunction "GND_H3") (pintype "bidirectional"))
      (node (ref "UXB2") (pin "H4") (pinfunction "GND_H4") (pintype "bidirectional"))
      (node (ref "X4") (pin "2") (pinfunction "K_2") (pintype "passive"))
      (node (ref "X5") (pin "GND") (pinfunction "GND_GND") (pintype "bidirectional"))
    )
    (net (code "8") (name "GPRS_PG") (class "Default")
      (node (ref "IC1") (pin "2") (pinfunction "PC13_2") (pintype "bidirectional"))
      (node (ref "R12") (pin "1") (pinfunction "1_1") (pintype "passive"))
    )
    (net (code "9") (name "GPRS_PWREN") (class "Default")
      (node (ref "IC1") (pin "29") (pinfunction "PA8_29") (pintype "bidirectional"))
      (node (ref "IC6") (pin "1") (pinfunction "EN_1") (pintype "bidirectional"))
    )
    (net (code "10") (name "GPRS_PWRKEY") (class "Default")
      (node (ref "IC1") (pin "30") (pinfunction "PA9_30") (pintype "bidirectional"))
      (node (ref "R6") (pin "2") (pinfunction "2_2") (pintype "passive"))
      (node (ref "T3") (pin "1") (pinfunction "G_1") (pintype "passive"))
    )
    (net (code "11") (name "GPRS_RXD2") (class "Default")
      (node (ref "IC5") (pin "28") (pinfunction "RXD_AUX_28") (pintype "bidirectional"))
    )
    (net (code "12") (name "GPRS_SLEEP") (class "Default")
      (node (ref "IC1") (pin "14") (pinfunction "PA4_14") (pintype "bidirectional"))
      (node (ref "IC5") (pin "19") (pinfunction "DTR_19") (pintype "bidirectional"))
    )
    (net (code "13") (name "GPRS_TXD2") (class "Default")
      (node (ref "IC5") (pin "29") (pinfunction "TXD_AUX_29") (pintype "bidirectional"))
    )
    (net (code "14") (name "ID") (class "Default")
      (node (ref "IC1") (pin "31") (pinfunction "PA10_31") (pintype "bidirectional"))
      (node (ref "UXB1") (pin "ID") (pinfunction "ID_ID") (pintype "bidirectional"))
      (node (ref "UXB2") (pin "ID") (pinfunction "ID_ID") (pintype "bidirectional"))
    )
    (net (code "15") (name "IRQ") (class "Default")
      (node (ref "IC1") (pin "33") (pinfunction "PA12_33") (pintype "bidirectional"))
      (node (ref "UXB1") (pin "IRQ") (pinfunction "IRQ_IRQ") (pintype "bidirectional"))
      (node (ref "UXB2") (pin "IRQ") (pinfunction "IRQ_IRQ") (pintype "bidirectional"))
    )
    (net (code "16") (name "LED_STAT") (class "Default")
      (node (ref "IC1") (pin "21") (pinfunction "PB10_21") (pintype "bidirectional"))
      (node (ref "R9") (pin "2") (pinfunction "2_2") (pintype "passive"))
    )
    (net (code "17") (name "NRST") (class "Default")
      (node (ref "DEBUG") (pin "NRESET") (pinfunction "NRESET_NRESET") (pintype "bidirectional"))
      (node (ref "IC1") (pin "7") (pinfunction "NRST_7") (pintype "bidirectional"))
    )
    (net (code "18") (name "Net-(ANT433-CENTER)") (class "Default")
      (node (ref "ANT433") (pin "C") (pinfunction "CENTER_C") (pintype "bidirectional"))
      (node (ref "CA2") (pin "1") (pinfunction "1_1") (pintype "passive"))
      (node (ref "CF") (pin "2") (pinfunction "2_2") (pintype "passive"))
      (node (ref "LF") (pin "1") (pinfunction "1_1") (pintype "passive"))
    )
    (net (code "19") (name "Net-(C3-Pad1)") (class "Default")
      (node (ref "C3") (pin "1") (pinfunction "1_1") (pintype "passive"))
      (node (ref "IC4") (pin "1") (pinfunction "VDD_ANA_1") (pintype "bidirectional"))
    )
    (net (code "20") (name "Net-(C32-Pad1)") (class "Default")
      (node (ref "C32") (pin "1") (pinfunction "1_1") (pintype "passive"))
      (node (ref "IC4") (pin "5") (pinfunction "VDD_ANA_5") (pintype "bidirectional"))
    )
    (net (code "21") (name "Net-(C36-Pad2)") (class "Default")
      (node (ref "C36") (pin "2") (pinfunction "2_2") (pintype "passive"))
      (node (ref "R19") (pin "2") (pinfunction "2_2") (pintype "passive"))
    )
    (net (code "22") (name "Net-(C66-Pad1)") (class "Default")
      (node (ref "C66") (pin "1") (pinfunction "1_1") (pintype "passive"))
      (node (ref "L7") (pin "1") (pinfunction "1_1") (pintype "passive"))
      (node (ref "X5") (pin "VBUS") (pinfunction "VBUS_VBUS") (pintype "bidirectional"))
    )
    (net (code "23") (name "Net-(CA1-Pad1)") (class "Default")
      (node (ref "CA1") (pin "1") (pinfunction "1_1") (pintype "passive"))
      (node (ref "CB2") (pin "2") (pinfunction "2_2") (pintype "passive"))
      (node (ref "CF") (pin "1") (pinfunction "1_1") (pintype "passive"))
      (node (ref "LB1") (pin "1") (pinfunction "1_1") (pintype "passive"))
      (node (ref "LF") (pin "2") (pinfunction "2_2") (pintype "passive"))
    )
    (net (code "24") (name "Net-(CB2-Pad1)") (class "Default")
      (node (ref "CB2") (pin "1") (pinfunction "1_1") (pintype "passive"))
      (node (ref "CM2") (pin "1") (pinfunction "1_1") (pintype "passive"))
      (node (ref "LB2") (pin "1") (pinfunction "1_1") (pintype "passive"))
      (node (ref "LT2") (pin "1") (pinfunction "1_1") (pintype "passive"))
    )
    (net (code "25") (name "Net-(CHG-PadA)") (class "Default")
      (node (ref "CHG") (pin "A") (pinfunction "A_A") (pintype "passive"))
      (node (ref "R8") (pin "1") (pinfunction "1_1") (pintype "passive"))
    )
    (net (code "26") (name "Net-(CM1-Pad1)") (class "Default")
      (node (ref "CM1") (pin "1") (pinfunction "1_1") (pintype "passive"))
      (node (ref "LB1") (pin "2") (pinfunction "2_2") (pintype "passive"))
      (node (ref "LT1") (pin "1") (pinfunction "1_1") (pintype "passive"))
    )
    (net (code "27") (name "Net-(CT1-Pad2)") (class "Default")
      (node (ref "CT1") (pin "2") (pinfunction "2_2") (pintype "passive"))
      (node (ref "LT1") (pin "2") (pinfunction "2_2") (pintype "passive"))
    )
    (net (code "28") (name "Net-(CT2-Pad2)") (class "Default")
      (node (ref "CT2") (pin "2") (pinfunction "2_2") (pintype "passive"))
      (node (ref "LT2") (pin "2") (pinfunction "2_2") (pintype "passive"))
    )
    (net (code "29") (name "Net-(D4-K1)") (class "Default")
      (node (ref "C24") (pin "1") (pinfunction "1_1") (pintype "passive"))
      (node (ref "C28") (pin "1") (pinfunction "1_1") (pintype "passive"))
      (node (ref "D4") (pin "1") (pinfunction "K1_1") (pintype "passive"))
      (node (ref "IC5") (pin "14") (pinfunction "SIM_VDD_14") (pintype "bidirectional"))
      (node (ref "SIM_CARD") (pin "C1") (pinfunction "C1_C1") (pintype "bidirectional"))
    )
    (net (code "30") (name "Net-(D4-K2)") (class "Default")
      (node (ref "C25") (pin "1") (pinfunction "1_1") (pintype "passive"))
      (node (ref "D4") (pin "2") (pinfunction "K2_2") (pintype "passive"))
      (node (ref "R7") (pin "1") (pinfunction "1_1") (pintype "passive"))
      (node (ref "SIM_CARD") (pin "C7") (pinfunction "C7_C7") (pintype "bidirectional"))
    )
    (net (code "31") (name "Net-(D5-K1)") (class "Default")
      (node (ref "C27") (pin "1") (pinfunction "1_1") (pintype "passive"))
      (node (ref "D5") (pin "1") (pinfunction "K1_1") (pintype "passive"))
      (node (ref "R11") (pin "1") (pinfunction "1_1") (pintype "passive"))
      (node (ref "SIM_CARD") (pin "C3") (pinfunction "C3_C3") (pintype "bidirectional"))
    )
    (net (code "32") (name "Net-(D5-K2)") (class "Default")
      (node (ref "C26") (pin "1") (pinfunction "1_1") (pintype "passive"))
      (node (ref "D5") (pin "2") (pinfunction "K2_2") (pintype "passive"))
      (node (ref "R10") (pin "1") (pinfunction "1_1") (pintype "passive"))
      (node (ref "SIM_CARD") (pin "C2") (pinfunction "C2_C2") (pintype "bidirectional"))
    )
    (net (code "33") (name "Net-(GSM-CENTER)") (class "Default")
      (node (ref "GSM") (pin "C") (pinfunction "CENTER_C") (pintype "bidirectional"))
      (node (ref "IC5") (pin "35") (pinfunction "RF_ANT_35") (pintype "bidirectional"))
    )
    (net (code "34") (name "Net-(IC1-BOOT0)") (class "Default")
      (node (ref "IC1") (pin "44") (pinfunction "BOOT0_44") (pintype "bidirectional"))
      (node (ref "R1") (pin "2") (pinfunction "2_2") (pintype "passive"))
    )
    (net (code "35") (name "Net-(IC1-PC14-OSC32_IN)") (class "Default")
      (node (ref "C14") (pin "1") (pinfunction "1_1") (pintype "passive"))
      (node (ref "IC1") (pin "3") (pinfunction "PC14-OSC32_IN_3") (pintype "bidirectional"))
      (node (ref "Q2") (pin "2") (pinfunction "2_2") (pintype "passive"))
    )
    (net (code "36") (name "Net-(IC1-PC15-OSC32_OUT)") (class "Default")
      (node (ref "C15") (pin "1") (pinfunction "1_1") (pintype "passive"))
      (node (ref "IC1") (pin "4") (pinfunction "PC15-OSC32_OUT_4") (pintype "bidirectional"))
      (node (ref "Q2") (pin "1") (pinfunction "1_1") (pintype "passive"))
    )
    (net (code "37") (name "Net-(IC1-PH0-OSC_IN)") (class "Default")
      (node (ref "C5") (pin "1") (pinfunction "1_1") (pintype "passive"))
      (node (ref "IC1") (pin "5") (pinfunction "PH0-OSC_IN_5") (pintype "bidirectional"))
      (node (ref "Q1") (pin "3") (pinfunction "2_3") (pintype "passive"))
    )
    (net (code "38") (name "Net-(IC1-PH1-OSC_OUT)") (class "Default")
      (node (ref "C6") (pin "1") (pinfunction "1_1") (pintype "passive"))
      (node (ref "IC1") (pin "6") (pinfunction "PH1-OSC_OUT_6") (pintype "bidirectional"))
      (node (ref "Q1") (pin "1") (pinfunction "1_1") (pintype "passive"))
    )
    (net (code "39") (name "Net-(IC1-VCAP1)") (class "Default")
      (node (ref "C22") (pin "1") (pinfunction "1_1") (pintype "passive"))
      (node (ref "IC1") (pin "22") (pinfunction "VCAP1_22") (pintype "bidirectional"))
    )
    (net (code "40") (name "Net-(IC1-VDDA{slash}VREF+)") (class "Default")
      (node (ref "C1") (pin "1") (pinfunction "1_1") (pintype "passive"))
      (node (ref "C2") (pin "1") (pinfunction "1_1") (pintype "passive"))
      (node (ref "IC1") (pin "9") (pinfunction "VDDA/VREF+_9") (pintype "bidirectional"))
      (node (ref "L2") (pin "2") (pinfunction "2_2") (pintype "passive"))
    )
    (net (code "41") (name "Net-(IC3-FB)") (class "Default")
      (node (ref "C10") (pin "2") (pinfunction "2_2") (pintype "passive"))
      (node (ref "C12") (pin "1") (pinfunction "1_1") (pintype "passive"))
      (node (ref "IC3") (pin "4") (pinfunction "FB_4") (pintype "bidirectional"))
      (node (ref "R3") (pin "1") (pinfunction "1_1") (pintype "passive"))
      (node (ref "R4") (pin "2") (pinfunction "2_2") (pintype "passive"))
    )
    (net (code "42") (name "Net-(IC3-SW)") (class "Default")
      (node (ref "IC3") (pin "5") (pinfunction "SW_5") (pintype "bidirectional"))
      (node (ref "L1") (pin "1") (pinfunction "1_1") (pintype "passive"))
    )
    (net (code "43") (name "Net-(IC4-ANTN)") (class "Default")
      (node (ref "CC2") (pin "1") (pinfunction "1_1") (pintype "passive"))
      (node (ref "CT2") (pin "1") (pinfunction "1_1") (pintype "passive"))
      (node (ref "IC4") (pin "4") (pinfunction "ANTN_4") (pintype "bidirectional"))
      (node (ref "LC2") (pin "1") (pinfunction "1_1") (pintype "passive"))
    )
    (net (code "44") (name "Net-(IC4-ANTP)") (class "Default")
      (node (ref "CC1") (pin "1") (pinfunction "1_1") (pintype "passive"))
      (node (ref "CT1") (pin "1") (pinfunction "1_1") (pintype "passive"))
      (node (ref "IC4") (pin "3") (pinfunction "ANTP_3") (pintype "bidirectional"))
      (node (ref "LC1") (pin "1") (pinfunction "1_1") (pintype "passive"))
    )
    (net (code "45") (name "Net-(IC4-CLK16N)") (class "Default")
      (node (ref "CC4") (pin "1") (pinfunction "1_1") (pintype "passive"))
      (node (ref "IC4") (pin "19") (pinfunction "CLK16N_19") (pintype "bidirectional"))
      (node (ref "Q3") (pin "1") (pinfunction "1_1") (pintype "passive"))
    )
    (net (code "46") (name "Net-(IC4-CLK16P)") (class "Default")
      (node (ref "CC3") (pin "1") (pinfunction "1_1") (pintype "passive"))
      (node (ref "IC4") (pin "20") (pinfunction "CLK16P_20") (pintype "bidirectional"))
      (node (ref "Q3") (pin "3") (pinfunction "2_3") (pintype "passive"))
    )
    (net (code "47") (name "Net-(IC4-L1)") (class "Default")
      (node (ref "IC4") (pin "7") (pinfunction "L2_7") (pintype "bidirectional"))
      (node (ref "IC4") (pin "8") (pinfunction "L1_8") (pintype "bidirectional"))
    )
    (net (code "48") (name "Net-(IC5-NETLIGHT)") (class "Default")
      (node (ref "IC5") (pin "16") (pinfunction "NETLIGHT_16") (pintype "bidirectional"))
      (node (ref "R17") (pin "1") (pinfunction "1_1") (pintype "passive"))
      (node (ref "T2") (pin "1") (pinfunction "G_1") (pintype "passive"))
    )
    (net (code "49") (name "Net-(IC5-PWRKEY)") (class "Default")
      (node (ref "IC5") (pin "7") (pinfunction "PWRKEY_7") (pintype "bidirectional"))
      (node (ref "T3") (pin "3") (pinfunction "D_3") (pintype "passive"))
    )
    (net (code "50") (name "Net-(IC5-RFTXMON)") (class "Default")
      (node (ref "IC5") (pin "25") (pinfunction "RFTXMON_25") (pintype "bidirectional"))
      (node (ref "R18") (pin "1") (pinfunction "1_1") (pintype "passive"))
      (node (ref "T1") (pin "1") (pinfunction "G_1") (pintype "passive"))
    )
    (net (code "51") (name "Net-(IC5-SIM_CLK)") (class "Default")
      (node (ref "IC5") (pin "13") (pinfunction "SIM_CLK_13") (pintype "bidirectional"))
      (node (ref "R11") (pin "2") (pinfunction "2_2") (pintype "passive"))
    )
    (net (code "52") (name "Net-(IC5-SIM_DATA)") (class "Default")
      (node (ref "IC5") (pin "11") (pinfunction "SIM_DATA_11") (pintype "bidirectional"))
      (node (ref "R7") (pin "2") (pinfunction "2_2") (pintype "passive"))
    )
    (net (code "53") (name "Net-(IC5-SIM_GND)") (class "Default")
      (node (ref "C28") (pin "2") (pinfunction "2_2") (pintype "passive"))
      (node (ref "IC5") (pin "10") (pinfunction "SIM_GND_10") (pintype "bidirectional"))
      (node (ref "SIM_CARD") (pin "C5") (pinfunction "C5_C5") (pintype "bidirectional"))
    )
    (net (code "54") (name "Net-(IC5-SIM_RST)") (class "Default")
      (node (ref "IC5") (pin "12") (pinfunction "SIM_RST_12") (pintype "bidirectional"))
      (node (ref "R10") (pin "2") (pinfunction "2_2") (pintype "passive"))
    )
    (net (code "55") (name "Net-(IC5-VDD_EXT)") (class "Default")
      (node (ref "C29") (pin "1") (pinfunction "1_1") (pintype "passive"))
      (node (ref "IC5") (pin "24") (pinfunction "VDD_EXT_24") (pintype "bidirectional"))
      (node (ref "R12") (pin "2") (pinfunction "2_2") (pintype "passive"))
    )
    (net (code "56") (name "Net-(IC5-VRTC)") (class "Default")
      (node (ref "D3") (pin "C") (pinfunction "C_C") (pintype "passive"))
      (node (ref "IC5") (pin "44") (pinfunction "VRTC_44") (pintype "bidirectional"))
    )
    (net (code "57") (name "Net-(IC6-FB)") (class "Default")
      (node (ref "IC6") (pin "6") (pinfunction "FB_6") (pintype "bidirectional"))
      (node (ref "R23") (pin "1") (pinfunction "1_1") (pintype "passive"))
      (node (ref "R24") (pin "2") (pinfunction "2_2") (pintype "passive"))
    )
    (net (code "58") (name "Net-(IC6-LX)") (class "Default")
      (node (ref "IC6") (pin "5") (pinfunction "LX_5") (pintype "bidirectional"))
      (node (ref "L5") (pin "2") (pinfunction "2_2") (pintype "passive"))
    )
    (net (code "59") (name "Net-(IC8-BOOT)") (class "Default")
      (node (ref "C34") (pin "1") (pinfunction "1_1") (pintype "passive"))
      (node (ref "IC8") (pin "1") (pinfunction "BOOT_1") (pintype "bidirectional"))
    )
    (net (code "60") (name "Net-(IC8-COMP)") (class "Default")
      (node (ref "C35") (pin "1") (pinfunction "1_1") (pintype "passive"))
      (node (ref "C36") (pin "1") (pinfunction "1_1") (pintype "passive"))
      (node (ref "IC8") (pin "6") (pinfunction "COMP_6") (pintype "bidirectional"))
    )
    (net (code "61") (name "Net-(IC8-EN)") (class "Default")
      (node (ref "IC8") (pin "3") (pinfunction "EN_3") (pintype "bidirectional"))
      (node (ref "R14") (pin "1") (pinfunction "1_1") (pintype "passive"))
      (node (ref "R15") (pin "2") (pinfunction "2_2") (pintype "passive"))
    )
    (net (code "62") (name "Net-(IC8-PH)") (class "Default")
      (node (ref "C34") (pin "2") (pinfunction "2_2") (pintype "passive"))
      (node (ref "IC8") (pin "8") (pinfunction "PH_8") (pintype "bidirectional"))
      (node (ref "L4") (pin "2") (pinfunction "2_2") (pintype "passive"))
    )
    (net (code "63") (name "Net-(IC8-RT{slash}CLK)") (class "Default")
      (node (ref "IC8") (pin "4") (pinfunction "RT/CLK_4") (pintype "bidirectional"))
      (node (ref "R20") (pin "2") (pinfunction "2_2") (pintype "passive"))
    )
    (net (code "64") (name "Net-(IC8-VIN)") (class "Default")
      (node (ref "C37") (pin "1") (pinfunction "1_1") (pintype "passive"))
      (node (ref "C39") (pin "1") (pinfunction "1_1") (pintype "passive"))
      (node (ref "D1") (pin "C") (pinfunction "C_C") (pintype "passive"))
      (node (ref "IC8") (pin "2") (pinfunction "VIN_2") (pintype "bidirectional"))
      (node (ref "R14") (pin "2") (pinfunction "2_2") (pintype "passive"))
      (node (ref "R21") (pin "2") (pinfunction "2_2") (pintype "passive"))
      (node (ref "X4") (pin "1") (pinfunction "K_1") (pintype "passive"))
    )
    (net (code "65") (name "Net-(IC8-VSENSE)") (class "Default")
      (node (ref "IC8") (pin "5") (pinfunction "VSENSE_5") (pintype "bidirectional"))
      (node (ref "R2") (pin "1") (pinfunction "1_1") (pintype "passive"))
      (node (ref "R5") (pin "2") (pinfunction "2_2") (pintype "passive"))
    )
    (net (code "66") (name "Net-(IC11-DM)") (class "Default")
      (node (ref "IC11") (pin "5") (pinfunction "DM_5") (pintype "bidirectional"))
      (node (ref "X5") (pin "D-") (pinfunction "D-_D-") (pintype "bidirectional"))
    )
    (net (code "67") (name "Net-(IC11-DP)") (class "Default")
      (node (ref "IC11") (pin "4") (pinfunction "DP_4") (pintype "bidirectional"))
      (node (ref "X5") (pin "D+") (pinfunction "D+_D+") (pintype "bidirectional"))
    )
    (net (code "68") (name "Net-(IC11-VDD)") (class "Default")
      (node (ref "C68") (pin "1") (pinfunction "1_1") (pintype "passive"))
      (node (ref "IC11") (pin "6") (pinfunction "VDD_6") (pintype "bidirectional"))
    )
    (net (code "69") (name "Net-(LED1-PadA)") (class "Default")
      (node (ref "LED1") (pin "A") (pinfunction "A_A") (pintype "passive"))
      (node (ref "R13") (pin "1") (pinfunction "1_1") (pintype "passive"))
    )
    (net (code "70") (name "Net-(LED2-PadA)") (class "Default")
      (node (ref "LED2") (pin "A") (pinfunction "A_A") (pintype "passive"))
      (node (ref "R16") (pin "1") (pinfunction "1_1") (pintype "passive"))
    )
    (net (code "71") (name "Net-(R9-Pad1)") (class "Default")
      (node (ref "R9") (pin "1") (pinfunction "1_1") (pintype "passive"))
      (node (ref "STAT") (pin "A") (pinfunction "A_A") (pintype "passive"))
    )
    (net (code "72") (name "Net-(T1-D)") (class "Default")
      (node (ref "LED2") (pin "C") (pinfunction "C_C") (pintype "passive"))
      (node (ref "T1") (pin "3") (pinfunction "D_3") (pintype "passive"))
    )
    (net (code "73") (name "Net-(T2-D)") (class "Default")
      (node (ref "LED1") (pin "C") (pinfunction "C_C") (pintype "passive"))
      (node (ref "T2") (pin "3") (pinfunction "D_3") (pintype "passive"))
    )
    (net (code "74") (name "RADIO_CS") (class "Default")
      (node (ref "IC1") (pin "20") (pinfunction "PB2_20") (pintype "bidirectional"))
      (node (ref "IC4") (pin "10") (pinfunction "SEL_10") (pintype "bidirectional"))
    )
    (net (code "75") (name "RADIO_IRQ") (class "Default")
      (node (ref "IC1") (pin "19") (pinfunction "PB1_19") (pintype "bidirectional"))
      (node (ref "IC4") (pin "14") (pinfunction "IRQ_14") (pintype "bidirectional"))
    )
    (net (code "76") (name "SCL") (class "Default")
      (node (ref "IC1") (pin "45") (pinfunction "PB8_45") (pintype "bidirectional"))
      (node (ref "IC7") (pin "6") (pinfunction "SCL_6") (pintype "input"))
      (node (ref "JP1") (pin "1") (pinfunction "1_1") (pintype "passive"))
      (node (ref "UXB1") (pin "SCL") (pinfunction "SCL_SCL") (pintype "bidirectional"))
      (node (ref "UXB2") (pin "SCL") (pinfunction "SCL_SCL") (pintype "bidirectional"))
    )
    (net (code "77") (name "SDA") (class "Default")
      (node (ref "IC1") (pin "46") (pinfunction "PB9_46") (pintype "bidirectional"))
      (node (ref "IC7") (pin "5") (pinfunction "SDA_5") (pintype "bidirectional"))
      (node (ref "JP1") (pin "2") (pinfunction "2_2") (pintype "passive"))
      (node (ref "UXB1") (pin "SDA") (pinfunction "SDA_SDA") (pintype "bidirectional"))
      (node (ref "UXB2") (pin "SDA") (pinfunction "SDA_SDA") (pintype "bidirectional"))
    )
    (net (code "78") (name "SIM_CD") (class "Default")
      (node (ref "SIM_CARD") (pin "CD") (pinfunction "CD_CD") (pintype "bidirectional"))
    )
    (net (code "79") (name "SPI2_MISO") (class "Default")
      (node (ref "IC1") (pin "27") (pinfunction "PB14_27") (pintype "bidirectional"))
      (node (ref "IC2") (pin "2") (pinfunction "SO_2") (pintype "bidirectional"))
      (node (ref "IC4") (pin "12") (pinfunction "MISO_12") (pintype "bidirectional"))
    )
    (net (code "80") (name "SPI2_MOSI") (class "Default")
      (node (ref "IC1") (pin "28") (pinfunction "PB15_28") (pintype "bidirectional"))
      (node (ref "IC2") (pin "5") (pinfunction "SI_5") (pintype "bidirectional"))
      (node (ref "IC4") (pin "13") (pinfunction "MOSI_13") (pintype "bidirectional"))
    )
    (net (code "81") (name "SPI2_SCK") (class "Default")
      (node (ref "IC1") (pin "26") (pinfunction "PB13_26") (pintype "bidirectional"))
      (node (ref "IC2") (pin "6") (pinfunction "CLK_6") (pintype "bidirectional"))
      (node (ref "IC4") (pin "11") (pinfunction "CLK_11") (pintype "bidirectional"))
    )
    (net (code "82") (name "SWCLK") (class "Default")
      (node (ref "DEBUG") (pin "SWCLK/TCK") (pinfunction "SWCLK/TCK_SWCLK/TCK") (pintype "bidirectional"))
      (node (ref "IC1") (pin "37") (pinfunction "PA14_37") (pintype "bidirectional"))
    )
    (net (code "83") (name "SWDIO") (class "Default")
      (node (ref "DEBUG") (pin "SWDIO/TMS") (pinfunction "SWDIO/TMS_SWDIO/TMS") (pintype "bidirectional"))
      (node (ref "IC1") (pin "34") (pinfunction "PA13_34") (pintype "bidirectional"))
    )
    (net (code "84") (name "USART2_CTS") (class "Default")
      (node (ref "IC1") (pin "10") (pinfunction "PA0_10") (pintype "bidirectional"))
      (node (ref "IC5") (pin "22") (pinfunction "CTS_22") (pintype "bidirectional"))
    )
    (net (code "85") (name "USART2_RTS") (class "Default")
      (node (ref "IC1") (pin "11") (pinfunction "PA1_11") (pintype "bidirectional"))
      (node (ref "IC5") (pin "23") (pinfunction "RTS_23") (pintype "bidirectional"))
    )
    (net (code "86") (name "USART2_RX") (class "Default")
      (node (ref "IC1") (pin "13") (pinfunction "PA3_13") (pintype "bidirectional"))
      (node (ref "IC5") (pin "17") (pinfunction "TXD_17") (pintype "bidirectional"))
    )
    (net (code "87") (name "USART2_TX") (class "Default")
      (node (ref "IC1") (pin "12") (pinfunction "PA2_12") (pintype "bidirectional"))
      (node (ref "IC5") (pin "18") (pinfunction "RXD_18") (pintype "bidirectional"))
    )
    (net (code "88") (name "USB_VBUS") (class "Default")
      (node (ref "C67") (pin "1") (pinfunction "1_1") (pintype "passive"))
      (node (ref "IC11") (pin "7") (pinfunction "REGIN_7") (pintype "bidirectional"))
      (node (ref "IC11") (pin "8") (pinfunction "VBUS_8") (pintype "bidirectional"))
      (node (ref "IC9") (pin "1") (pinfunction "INA_1") (pintype "bidirectional"))
      (node (ref "L7") (pin "2") (pinfunction "2_2") (pintype "passive"))
    )
    (net (code "89") (name "VBACKUP") (class "Default")
      (node (ref "B1") (pin "POS") (pinfunction "+_POS") (pintype "passive"))
      (node (ref "D3") (pin "A") (pinfunction "A_A") (pintype "passive"))
      (node (ref "IC1") (pin "1") (pinfunction "VBAT_1") (pintype "bidirectional"))
    )
    (net (code "90") (name "VBUS") (class "Default")
      (node (ref "C11") (pin "1") (pinfunction "1_1") (pintype "passive"))
      (node (ref "C30") (pin "1") (pinfunction "1_1") (pintype "passive"))
      (node (ref "C40") (pin "1") (pinfunction "1_1") (pintype "passive"))
      (node (ref "IC3") (pin "1") (pinfunction "VIN_1") (pintype "bidirectional"))
      (node (ref "IC3") (pin "3") (pinfunction "EN_3") (pintype "bidirectional"))
      (node (ref "IC6") (pin "3") (pinfunction "VIN_3") (pintype "bidirectional"))
      (node (ref "IC9") (pin "10") (pinfunction "OUTA_10") (pintype "bidirectional"))
      (node (ref "IC9") (pin "6") (pinfunction "OUTB_6") (pintype "bidirectional"))
      (node (ref "JP1") (pin "3") (pinfunction "3_3") (pintype "passive"))
      (node (ref "R25") (pin "1") (pinfunction "1_1") (pintype "passive"))
      (node (ref "UXB1") (pin "VBUS") (pinfunction "VBUS_VBUS") (pintype "bidirectional"))
      (node (ref "UXB2") (pin "VBUS") (pinfunction "VBUS_VBUS") (pintype "bidirectional"))
    )
    (net (code "91") (name "VBUS_USENSE") (class "Default")
      (node (ref "IC1") (pin "16") (pinfunction "PA6_16") (pintype "bidirectional"))
      (node (ref "R25") (pin "2") (pinfunction "2_2") (pintype "passive"))
      (node (ref "R26") (pin "2") (pinfunction "2_2") (pintype "passive"))
    )
    (net (code "92") (name "VDD28") (class "Default")
      (node (ref "C10") (pin "1") (pinfunction "1_1") (pintype "passive"))
      (node (ref "C13") (pin "1") (pinfunction "1_1") (pintype "passive"))
      (node (ref "C16") (pin "1") (pinfunction "1_1") (pintype "passive"))
      (node (ref "C17") (pin "1") (pinfunction "1_1") (pintype "passive"))
      (node (ref "C21") (pin "1") (pinfunction "1_1") (pintype "passive"))
      (node (ref "C33") (pin "1") (pinfunction "1_1") (pintype "passive"))
      (node (ref "C4") (pin "1") (pinfunction "1_1") (pintype "passive"))
      (node (ref "C7") (pin "1") (pinfunction "1_1") (pintype "passive"))
      (node (ref "C8") (pin "1") (pinfunction "1_1") (pintype "passive"))
      (node (ref "C9") (pin "1") (pinfunction "1_1") (pintype "passive"))
      (node (ref "DEBUG") (pin "VCC") (pinfunction "VCC_VCC") (pintype "bidirectional"))
      (node (ref "IC1") (pin "24") (pinfunction "VDD_24") (pintype "bidirectional"))
      (node (ref "IC1") (pin "36") (pinfunction "VDD_36") (pintype "bidirectional"))
      (node (ref "IC1") (pin "48") (pinfunction "VDD_48") (pintype "bidirectional"))
      (node (ref "IC2") (pin "8") (pinfunction "VCC_8") (pintype "power_in"))
      (node (ref "IC4") (pin "16") (pinfunction "VDD_IO_16") (pintype "bidirectional"))
      (node (ref "IC7") (pin "8") (pinfunction "VCC_8") (pintype "power_in"))
      (node (ref "L1") (pin "2") (pinfunction "2_2") (pintype "passive"))
      (node (ref "L2") (pin "1") (pinfunction "1_1") (pintype "passive"))
      (node (ref "R3") (pin "2") (pinfunction "2_2") (pintype "passive"))
    )
    (net (code "93") (name "VDD39") (class "Default")
      (node (ref "C18") (pin "+") (pinfunction "+_+") (pintype "passive"))
      (node (ref "C19") (pin "+") (pinfunction "+_+") (pintype "passive"))
      (node (ref "C20") (pin "1") (pinfunction "1_1") (pintype "passive"))
      (node (ref "C23") (pin "1") (pinfunction "1_1") (pintype "passive"))
      (node (ref "C31") (pin "1") (pinfunction "1_1") (pintype "passive"))
      (node (ref "IC5") (pin "42") (pinfunction "VBAT_42") (pintype "bidirectional"))
      (node (ref "IC5") (pin "43") (pinfunction "VBAT_43") (pintype "bidirectional"))
      (node (ref "L5") (pin "1") (pinfunction "1_1") (pintype "passive"))
      (node (ref "R13") (pin "2") (pinfunction "2_2") (pintype "passive"))
      (node (ref "R16") (pin "2") (pinfunction "2_2") (pintype "passive"))
      (node (ref "R23") (pin "2") (pinfunction "2_2") (pintype "passive"))
    )
    (net (code "94") (name "VIN_5V") (class "Default")
      (node (ref "C38") (pin "1") (pinfunction "1_1") (pintype "passive"))
      (node (ref "IC9") (pin "5") (pinfunction "INB_5") (pintype "bidirectional"))
      (node (ref "L4") (pin "1") (pinfunction "1_1") (pintype "passive"))
      (node (ref "R2") (pin "2") (pinfunction "2_2") (pintype "passive"))
      (node (ref "R8") (pin "2") (pinfunction "2_2") (pintype "passive"))
    )
    (net (code "95") (name "VIN_USENSE") (class "Default")
      (node (ref "IC1") (pin "15") (pinfunction "PA5_15") (pintype "bidirectional"))
      (node (ref "R21") (pin "1") (pinfunction "1_1") (pintype "passive"))
      (node (ref "R22") (pin "2") (pinfunction "2_2") (pintype "passive"))
    )
    (net (code "96") (name "WAKEUP") (class "Default")
      (node (ref "IC1") (pin "32") (pinfunction "PA11_32") (pintype "bidirectional"))
      (node (ref "UXB1") (pin "WAKEUP") (pinfunction "WAKEUP_WAKEUP") (pintype "bidirectional"))
      (node (ref "UXB2") (pin "WAKEUP") (pinfunction "WAKEUP_WAKEUP") (pintype "bidirectional"))
    )
    (net (code "97") (name "unconnected-(DEBUG-PadNC{slash}TDI)") (class "Default")
      (node (ref "DEBUG") (pin "NC/TDI") (pinfunction "NC/TDI_NC/TDI") (pintype "bidirectional"))
    )
    (net (code "98") (name "unconnected-(DEBUG-PadSWO{slash}TDO)") (class "Default")
      (node (ref "DEBUG") (pin "SWO/TDO") (pinfunction "SWO/TDO_SWO/TDO") (pintype "bidirectional"))
    )
    (net (code "99") (name "unconnected-(IC1-PA7-Pad17)") (class "Default")
      (node (ref "IC1") (pin "17") (pinfunction "PA7_17") (pintype "bidirectional"))
    )
    (net (code "100") (name "unconnected-(IC1-PB0-Pad18)") (class "Default")
      (node (ref "IC1") (pin "18") (pinfunction "PB0_18") (pintype "bidirectional"))
    )
    (net (code "101") (name "unconnected-(IC2-HOLD-Pad7)") (class "Default")
      (node (ref "IC2") (pin "7") (pinfunction "HOLD_7") (pintype "bidirectional"))
    )
    (net (code "102") (name "unconnected-(IC2-WP-Pad3)") (class "Default")
      (node (ref "IC2") (pin "3") (pinfunction "WP_3") (pintype "bidirectional"))
    )
    (net (code "103") (name "unconnected-(IC4-FILT-Pad6)") (class "Default")
      (node (ref "IC4") (pin "6") (pinfunction "FILT_6") (pintype "bidirectional"))
    )
    (net (code "104") (name "unconnected-(IC4-SYSCLK-Pad9)") (class "Default")
      (node (ref "IC4") (pin "9") (pinfunction "SYSCLK_9") (pintype "bidirectional"))
    )
    (net (code "105") (name "unconnected-(IC4-TCXO_EN-Pad15)") (class "Default")
      (node (ref "IC4") (pin "15") (pinfunction "TCXO_EN_15") (pintype "bidirectional"))
    )
    (net (code "106") (name "unconnected-(IC5-ADC0-Pad9)") (class "Default")
      (node (ref "IC5") (pin "9") (pinfunction "ADC0_9") (pintype "bidirectional"))
    )
    (net (code "107") (name "unconnected-(IC5-AVDD-Pad8)") (class "Default")
      (node (ref "IC5") (pin "8") (pinfunction "AVDD_8") (pintype "bidirectional"))
    )
    (net (code "108") (name "unconnected-(IC5-BT_ANT-Pad26)") (class "Default")
      (node (ref "IC5") (pin "26") (pinfunction "BT_ANT_26") (pintype "bidirectional"))
    )
    (net (code "109") (name "unconnected-(IC5-DBG_RXD-Pad38)") (class "Default")
      (node (ref "IC5") (pin "38") (pinfunction "DBG_RXD_38") (pintype "bidirectional"))
    )
    (net (code "110") (name "unconnected-(IC5-DBG_TXD-Pad39)") (class "Default")
      (node (ref "IC5") (pin "39") (pinfunction "DBG_TXD_39") (pintype "bidirectional"))
    )
    (net (code "111") (name "unconnected-(IC5-DCD-Pad21)") (class "Default")
      (node (ref "IC5") (pin "21") (pinfunction "DCD_21") (pintype "bidirectional"))
    )
    (net (code "112") (name "unconnected-(IC5-MICN-Pad4)") (class "Default")
      (node (ref "IC5") (pin "4") (pinfunction "MICN_4") (pintype "bidirectional"))
    )
    (net (code "113") (name "unconnected-(IC5-MICP-Pad3)") (class "Default")
      (node (ref "IC5") (pin "3") (pinfunction "MICP_3") (pintype "bidirectional"))
    )
    (net (code "114") (name "unconnected-(IC5-PCM_CLK-Pad30)") (class "Default")
      (node (ref "IC5") (pin "30") (pinfunction "PCM_CLK_30") (pintype "bidirectional"))
    )
    (net (code "115") (name "unconnected-(IC5-PCM_IN-Pad32)") (class "Default")
      (node (ref "IC5") (pin "32") (pinfunction "PCM_IN_32") (pintype "bidirectional"))
    )
    (net (code "116") (name "unconnected-(IC5-PCM_OUT-Pad33)") (class "Default")
      (node (ref "IC5") (pin "33") (pinfunction "PCM_OUT_33") (pintype "bidirectional"))
    )
    (net (code "117") (name "unconnected-(IC5-PCM_SYNC-Pad31)") (class "Default")
      (node (ref "IC5") (pin "31") (pinfunction "PCM_SYNC_31") (pintype "bidirectional"))
    )
    (net (code "118") (name "unconnected-(IC5-RI-Pad20)") (class "Default")
      (node (ref "IC5") (pin "20") (pinfunction "RI_20") (pintype "bidirectional"))
    )
    (net (code "119") (name "unconnected-(IC5-SPK1N-Pad6)") (class "Default")
      (node (ref "IC5") (pin "6") (pinfunction "SPK1N_6") (pintype "bidirectional"))
    )
    (net (code "120") (name "unconnected-(IC5-SPK1P-Pad5)") (class "Default")
      (node (ref "IC5") (pin "5") (pinfunction "SPK1P_5") (pintype "bidirectional"))
    )
    (net (code "121") (name "unconnected-(IC5-SPK2P-Pad2)") (class "Default")
      (node (ref "IC5") (pin "2") (pinfunction "SPK2P_2") (pintype "bidirectional"))
    )
    (net (code "122") (name "unconnected-(IC7-WP-Pad7)") (class "Default")
      (node (ref "IC7") (pin "7") (pinfunction "WP_7") (pintype "input"))
    )
    (net (code "123") (name "unconnected-(IC9-STAT-Pad9)") (class "Default")
      (node (ref "IC9") (pin "9") (pinfunction "STAT_9") (pintype "bidirectional"))
    )
    (net (code "124") (name "unconnected-(IC11-CTS-Pad23)") (class "Default")
      (node (ref "IC11") (pin "23") (pinfunction "CTS_23") (pintype "bidirectional"))
    )
    (net (code "125") (name "unconnected-(IC11-DCD-Pad1)") (class "Default")
      (node (ref "IC11") (pin "1") (pinfunction "DCD_1") (pintype "bidirectional"))
    )
    (net (code "126") (name "unconnected-(IC11-DSR-Pad27)") (class "Default")
      (node (ref "IC11") (pin "27") (pinfunction "DSR_27") (pintype "bidirectional"))
    )
    (net (code "127") (name "unconnected-(IC11-DTR-Pad28)") (class "Default")
      (node (ref "IC11") (pin "28") (pinfunction "DTR_28") (pintype "bidirectional"))
    )
    (net (code "128") (name "unconnected-(IC11-NRST-Pad9)") (class "Default")
      (node (ref "IC11") (pin "9") (pinfunction "NRST_9") (pintype "bidirectional"))
    )
    (net (code "129") (name "unconnected-(IC11-NSUSPEND-Pad11)") (class "Default")
      (node (ref "IC11") (pin "11") (pinfunction "NSUSPEND_11") (pintype "bidirectional"))
    )
    (net (code "130") (name "unconnected-(IC11-RI-Pad2)") (class "Default")
      (node (ref "IC11") (pin "2") (pinfunction "RI_2") (pintype "bidirectional"))
    )
    (net (code "131") (name "unconnected-(IC11-RTS-Pad24)") (class "Default")
      (node (ref "IC11") (pin "24") (pinfunction "RTS_24") (pintype "bidirectional"))
    )
    (net (code "132") (name "unconnected-(IC11-SUSPEND-Pad12)") (class "Default")
      (node (ref "IC11") (pin "12") (pinfunction "SUSPEND_12") (pintype "bidirectional"))
    )
    (net (code "133") (name "unconnected-(SIM_CARD-PadC6)") (class "Default")
      (node (ref "SIM_CARD") (pin "C6") (pinfunction "C6_C6") (pintype "bidirectional"))
    )
  )
)
